# Patch_panel_module_-_CAT6.net
KiCad netlist of a schematic drawn in EAGLE
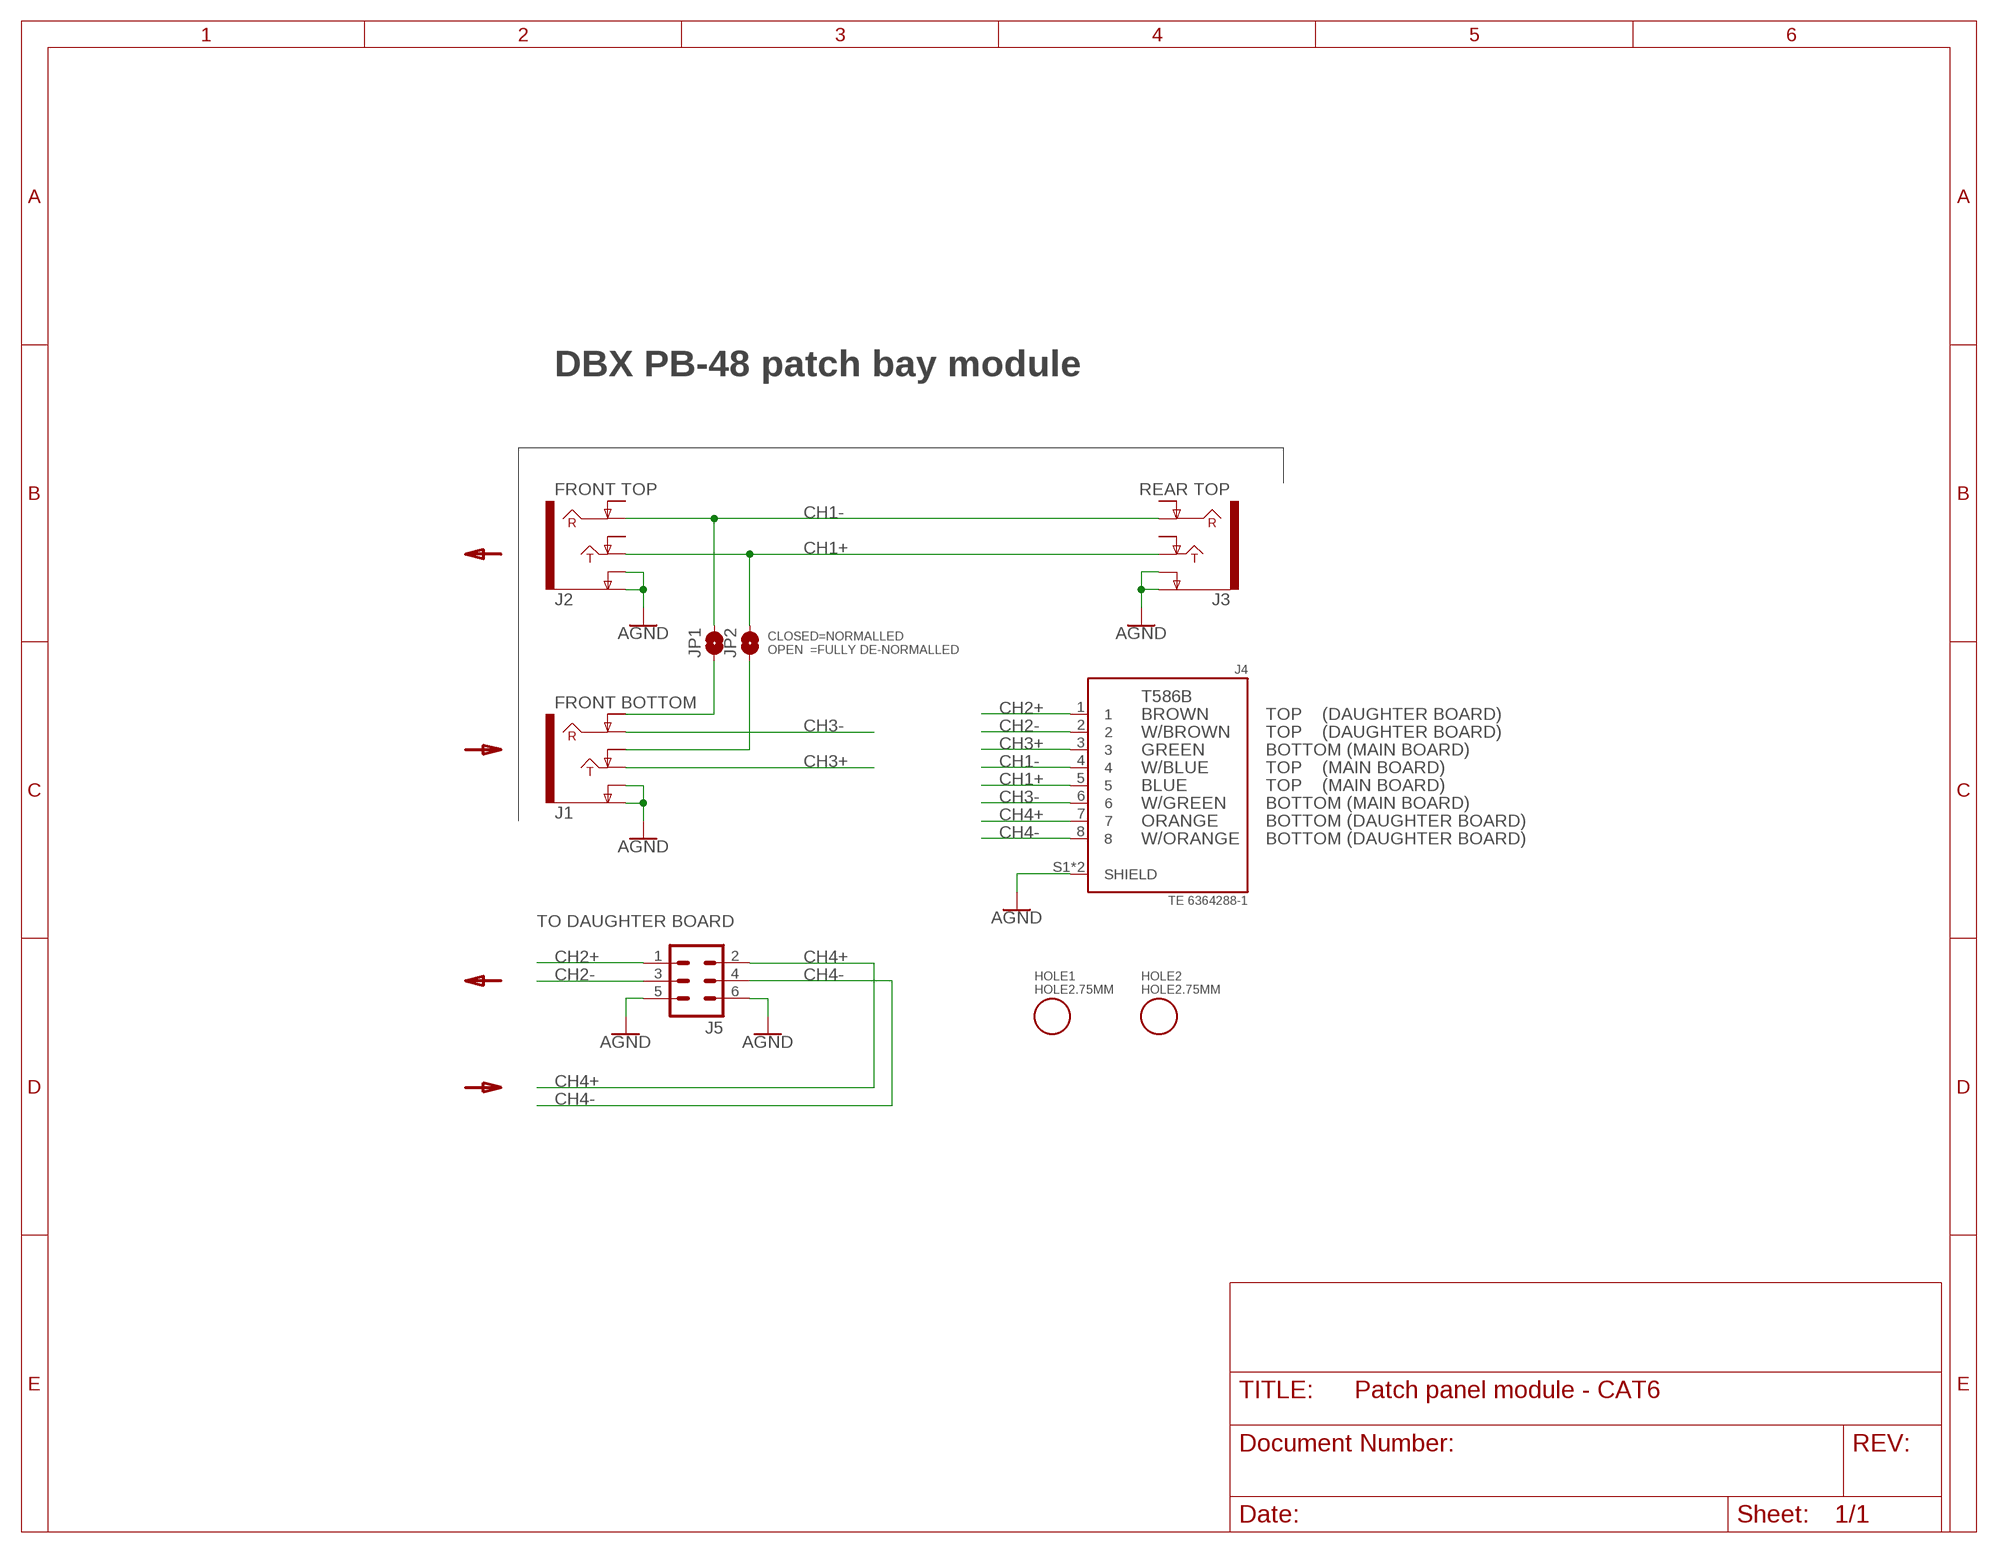
[diagram p0: schematic, sheet 1]

(export (version "E")
  (design (tool "Eeschema 10.0.6"))
  (components
    (comp (ref "HOLE1")
      (value "HOLE2.75MM")
      (footprint "eagle-import:HOLE-2.75MM")
      (libsource (lib "eagle-import") (part "HOLE2.75MM"))
    )
    (comp (ref "HOLE2")
      (value "HOLE2.75MM")
      (footprint "eagle-import:HOLE-2.75MM")
      (libsource (lib "eagle-import") (part "HOLE2.75MM"))
    )
    (comp (ref "J1")
      (value "FRONT BOTTOM")
      (footprint "eagle-import:NEUTRIK-NRJ6HF")
      (libsource (lib "eagle-import") (part "AUDIO_JACK_TRS_0.25{dblquote}_PTH_RA-NRJ6HM"))
    )
    (comp (ref "J2")
      (value "FRONT TOP")
      (footprint "eagle-import:NEUTRIK-NRJ6HF")
      (libsource (lib "eagle-import") (part "AUDIO_JACK_TRS_0.25{dblquote}_PTH_RA-NRJ6HM"))
    )
    (comp (ref "J3")
      (value "REAR TOP")
      (footprint "eagle-import:NEUTRIK-NRJ6HF")
      (libsource (lib "eagle-import") (part "AUDIO_JACK_TRS_0.25{dblquote}_PTH_RA-NRJ6HM"))
    )
    (comp (ref "J4")
      (value "TE 6364288-1")
      (footprint "eagle-import:RJ45-TE-6364288-1")
      (libsource (lib "eagle-import") (part "RJ45-SHIELDED-TE-6364288-1"))
    )
    (comp (ref "J5")
      (value "MA03-2")
      (footprint "eagle-import:MA03-2")
      (libsource (lib "eagle-import") (part "MA03-2"))
    )
    (comp (ref "JP1")
      (value "JUMPER-SMT_2_NO_NO-SILK_ROUND")
      (footprint "eagle-import:SMT-JUMPER_2_NO_NO-SILK_ROUND")
      (libsource (lib "eagle-import") (part "JUMPER-SMT_2_NO_NO-SILK_ROUND"))
    )
    (comp (ref "JP2")
      (value "JUMPER-SMT_2_NO_NO-SILK_ROUND")
      (footprint "eagle-import:SMT-JUMPER_2_NO_NO-SILK_ROUND")
      (libsource (lib "eagle-import") (part "JUMPER-SMT_2_NO_NO-SILK_ROUND"))
    )
  )
  (nets
    (net (code "1") (name "/CH1+") (class "Default")
      (node (ref "J2") (pin "T") (pinfunction "TIP_T") (pintype "bidirectional"))
      (node (ref "J3") (pin "T") (pinfunction "TIP_T") (pintype "bidirectional"))
      (node (ref "J4") (pin "5") (pinfunction "5_5") (pintype "bidirectional"))
      (node (ref "JP2") (pin "2") (pinfunction "2_2") (pintype "passive"))
    )
    (net (code "2") (name "/CH1-") (class "Default")
      (node (ref "J2") (pin "R") (pinfunction "RING_R") (pintype "bidirectional"))
      (node (ref "J3") (pin "R") (pinfunction "RING_R") (pintype "bidirectional"))
      (node (ref "J4") (pin "4") (pinfunction "4_4") (pintype "bidirectional"))
      (node (ref "JP1") (pin "2") (pinfunction "2_2") (pintype "passive"))
    )
    (net (code "3") (name "/CH2+") (class "Default")
      (node (ref "J4") (pin "1") (pinfunction "1_1") (pintype "bidirectional"))
      (node (ref "J5") (pin "1") (pinfunction "1_1") (pintype "passive"))
    )
    (net (code "4") (name "/CH2-") (class "Default")
      (node (ref "J4") (pin "2") (pinfunction "2_2") (pintype "bidirectional"))
      (node (ref "J5") (pin "3") (pinfunction "3_3") (pintype "passive"))
    )
    (net (code "5") (name "/CH3+") (class "Default")
      (node (ref "J1") (pin "T") (pinfunction "TIP_T") (pintype "bidirectional"))
      (node (ref "J4") (pin "3") (pinfunction "3_3") (pintype "bidirectional"))
    )
    (net (code "6") (name "/CH3-") (class "Default")
      (node (ref "J1") (pin "R") (pinfunction "RING_R") (pintype "bidirectional"))
      (node (ref "J4") (pin "6") (pinfunction "6_6") (pintype "bidirectional"))
    )
    (net (code "7") (name "/CH4+") (class "Default")
      (node (ref "J4") (pin "7") (pinfunction "7_7") (pintype "bidirectional"))
      (node (ref "J5") (pin "2") (pinfunction "2_2") (pintype "passive"))
    )
    (net (code "8") (name "/CH4-") (class "Default")
      (node (ref "J4") (pin "8") (pinfunction "8_8") (pintype "bidirectional"))
      (node (ref "J5") (pin "4") (pinfunction "4_4") (pintype "passive"))
    )
    (net (code "9") (name "AGND") (class "Default")
      (node (ref "J1") (pin "S") (pinfunction "EARTH_S") (pintype "bidirectional"))
      (node (ref "J1") (pin "SN") (pinfunction "EARTH-NORM_SN") (pintype "bidirectional"))
      (node (ref "J2") (pin "S") (pinfunction "EARTH_S") (pintype "bidirectional"))
      (node (ref "J2") (pin "SN") (pinfunction "EARTH-NORM_SN") (pintype "bidirectional"))
      (node (ref "J3") (pin "S") (pinfunction "EARTH_S") (pintype "bidirectional"))
      (node (ref "J3") (pin "SN") (pinfunction "EARTH-NORM_SN") (pintype "bidirectional"))
      (node (ref "J4") (pin "S1") (pinfunction "SHIELD_S1") (pintype "bidirectional"))
      (node (ref "J4") (pin "S2") (pinfunction "SHIELD_S2") (pintype "bidirectional"))
      (node (ref "J5") (pin "5") (pinfunction "5_5") (pintype "passive"))
      (node (ref "J5") (pin "6") (pinfunction "6_6") (pintype "passive"))
    )
    (net (code "10") (name "Net-(J1-RING-NORM)") (class "Default")
      (node (ref "J1") (pin "RN") (pinfunction "RING-NORM_RN") (pintype "bidirectional"))
      (node (ref "JP1") (pin "1") (pinfunction "1_1") (pintype "passive"))
    )
    (net (code "11") (name "Net-(J1-TIP-NORM)") (class "Default")
      (node (ref "J1") (pin "TN") (pinfunction "TIP-NORM_TN") (pintype "bidirectional"))
      (node (ref "JP2") (pin "1") (pinfunction "1_1") (pintype "passive"))
    )
    (net (code "12") (name "unconnected-(J2-RING-NORM-PadRN)") (class "Default")
      (node (ref "J2") (pin "RN") (pinfunction "RING-NORM_RN") (pintype "bidirectional"))
    )
    (net (code "13") (name "unconnected-(J2-TIP-NORM-PadTN)") (class "Default")
      (node (ref "J2") (pin "TN") (pinfunction "TIP-NORM_TN") (pintype "bidirectional"))
    )
    (net (code "14") (name "unconnected-(J3-RING-NORM-PadRN)") (class "Default")
      (node (ref "J3") (pin "RN") (pinfunction "RING-NORM_RN") (pintype "bidirectional"))
    )
    (net (code "15") (name "unconnected-(J3-TIP-NORM-PadTN)") (class "Default")
      (node (ref "J3") (pin "TN") (pinfunction "TIP-NORM_TN") (pintype "bidirectional"))
    )
  )
)
